# HVGA.net
KiCad netlist of a schematic drawn in Altium Designer
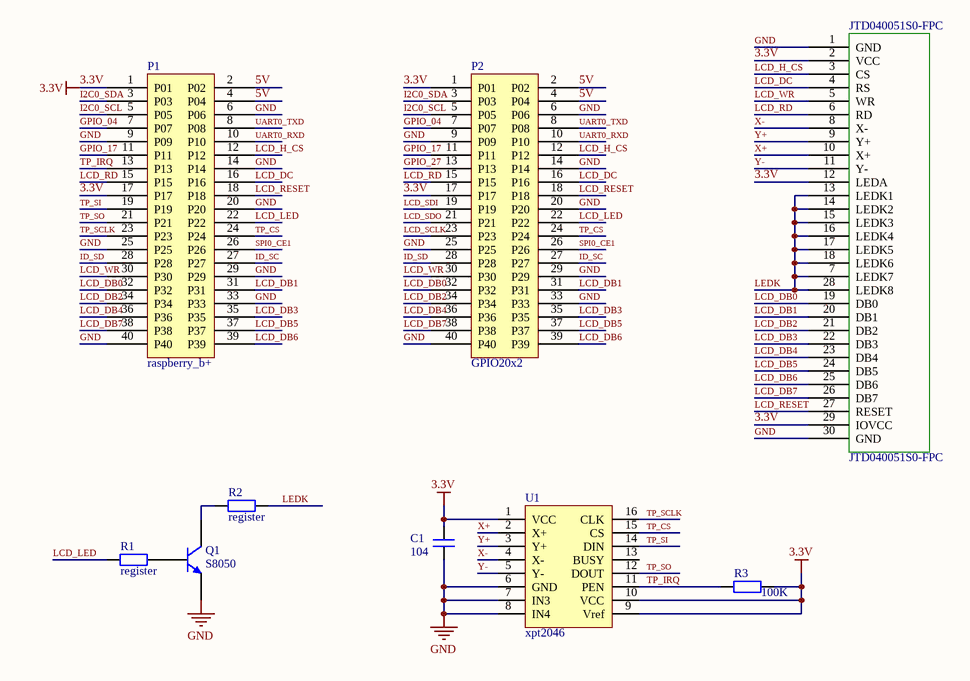
[diagram p0: HVGA.SchDoc]

(export (version "E")
  (design (tool "Eeschema 10.0.6"))
  (components
    (comp (ref "C1") (value "104") (footprint "1206") (libsource (lib "4.0_30P原理图库") (part "capacitor")))
    (comp (ref "JTD040051S0-FPC")
      (value "JTD040051S0-FPC")
      (footprint "JTD040051S0-FPC")
      (libsource (lib "4.0_30P原理图库") (part "JTD040051S0-FPC"))
    )
    (comp (ref "P1")
      (value "raspberry_b+")
      (footprint "raspberry_b+")
      (libsource (lib "4.0_30P原理图库") (part "raspberry_b+"))
    )
    (comp (ref "P2")
      (value "GPIO20x2")
      (footprint "GPIO20x2")
      (libsource (lib "4.0_30P原理图库") (part "raspberry_b+"))
    )
    (comp (ref "Q1") (value "S8050") (footprint "SOT23") (libsource (lib "4.0_30P原理图库") (part "S8050")))
    (comp (ref "R1") (value "register") (footprint "1206") (libsource (lib "4.0_30P原理图库") (part "register")))
    (comp (ref "R2") (value "register") (footprint "1206") (libsource (lib "4.0_30P原理图库") (part "register")))
    (comp (ref "R3") (value "100K") (footprint "1206") (libsource (lib "4.0_30P原理图库") (part "register")))
    (comp (ref "U1") (value "xpt2046") (footprint "TSSOP16") (libsource (lib "4.0_30P原理图库") (part "xpt2046")))
  )
  (nets
    (net (code "1") (name "/5V") (class "Default")
      (node (ref "P1") (pin "2") (pinfunction "P02_2") (pintype "passive"))
      (node (ref "P1") (pin "4") (pinfunction "P04_4") (pintype "passive"))
      (node (ref "P2") (pin "2") (pinfunction "P02_2") (pintype "passive"))
      (node (ref "P2") (pin "4") (pinfunction "P04_4") (pintype "passive"))
    )
    (net (code "2") (name "/GPIO_04") (class "Default")
      (node (ref "P1") (pin "7") (pinfunction "P07_7") (pintype "passive"))
      (node (ref "P2") (pin "7") (pinfunction "P07_7") (pintype "passive"))
    )
    (net (code "3") (name "/GPIO_17") (class "Default")
      (node (ref "P1") (pin "11") (pinfunction "P11_11") (pintype "passive"))
      (node (ref "P2") (pin "11") (pinfunction "P11_11") (pintype "passive"))
    )
    (net (code "4") (name "/GPIO_27") (class "Default")
      (node (ref "P2") (pin "13") (pinfunction "P13_13") (pintype "passive"))
    )
    (net (code "5") (name "/I2C0_SCL") (class "Default")
      (node (ref "P1") (pin "5") (pinfunction "P05_5") (pintype "passive"))
      (node (ref "P2") (pin "5") (pinfunction "P05_5") (pintype "passive"))
    )
    (net (code "6") (name "/I2C0_SDA") (class "Default")
      (node (ref "P1") (pin "3") (pinfunction "P03_3") (pintype "passive"))
      (node (ref "P2") (pin "3") (pinfunction "P03_3") (pintype "passive"))
    )
    (net (code "7") (name "/ID_SC") (class "Default")
      (node (ref "P1") (pin "27") (pinfunction "P27_27") (pintype "passive"))
      (node (ref "P2") (pin "27") (pinfunction "P27_27") (pintype "passive"))
    )
    (net (code "8") (name "/ID_SD") (class "Default")
      (node (ref "P1") (pin "28") (pinfunction "P28_28") (pintype "passive"))
      (node (ref "P2") (pin "28") (pinfunction "P28_28") (pintype "passive"))
    )
    (net (code "9") (name "/LCD_DB0") (class "Default")
      (node (ref "JTD040051S0-FPC") (pin "19") (pinfunction "DB0_19") (pintype "passive"))
      (node (ref "P1") (pin "32") (pinfunction "P32_32") (pintype "passive"))
      (node (ref "P2") (pin "32") (pinfunction "P32_32") (pintype "passive"))
    )
    (net (code "10") (name "/LCD_DB1") (class "Default")
      (node (ref "JTD040051S0-FPC") (pin "20") (pinfunction "DB1_20") (pintype "passive"))
      (node (ref "P1") (pin "31") (pinfunction "P31_31") (pintype "passive"))
      (node (ref "P2") (pin "31") (pinfunction "P31_31") (pintype "passive"))
    )
    (net (code "11") (name "/LCD_DB2") (class "Default")
      (node (ref "JTD040051S0-FPC") (pin "21") (pinfunction "DB2_21") (pintype "passive"))
      (node (ref "P1") (pin "34") (pinfunction "P34_34") (pintype "passive"))
      (node (ref "P2") (pin "34") (pinfunction "P34_34") (pintype "passive"))
    )
    (net (code "12") (name "/LCD_DB3") (class "Default")
      (node (ref "JTD040051S0-FPC") (pin "22") (pinfunction "DB3_22") (pintype "passive"))
      (node (ref "P1") (pin "35") (pinfunction "P35_35") (pintype "passive"))
      (node (ref "P2") (pin "35") (pinfunction "P35_35") (pintype "passive"))
    )
    (net (code "13") (name "/LCD_DB4") (class "Default")
      (node (ref "JTD040051S0-FPC") (pin "23") (pinfunction "DB4_23") (pintype "passive"))
      (node (ref "P1") (pin "36") (pinfunction "P36_36") (pintype "passive"))
      (node (ref "P2") (pin "36") (pinfunction "P36_36") (pintype "passive"))
    )
    (net (code "14") (name "/LCD_DB5") (class "Default")
      (node (ref "JTD040051S0-FPC") (pin "24") (pinfunction "DB5_24") (pintype "passive"))
      (node (ref "P1") (pin "37") (pinfunction "P37_37") (pintype "passive"))
      (node (ref "P2") (pin "37") (pinfunction "P37_37") (pintype "passive"))
    )
    (net (code "15") (name "/LCD_DB6") (class "Default")
      (node (ref "JTD040051S0-FPC") (pin "25") (pinfunction "DB6_25") (pintype "passive"))
      (node (ref "P1") (pin "39") (pinfunction "P39_39") (pintype "passive"))
      (node (ref "P2") (pin "39") (pinfunction "P39_39") (pintype "passive"))
    )
    (net (code "16") (name "/LCD_DB7") (class "Default")
      (node (ref "JTD040051S0-FPC") (pin "26") (pinfunction "DB7_26") (pintype "passive"))
      (node (ref "P1") (pin "38") (pinfunction "P38_38") (pintype "passive"))
      (node (ref "P2") (pin "38") (pinfunction "P38_38") (pintype "passive"))
    )
    (net (code "17") (name "/LCD_DC") (class "Default")
      (node (ref "JTD040051S0-FPC") (pin "4") (pinfunction "RS_4") (pintype "passive"))
      (node (ref "P1") (pin "16") (pinfunction "P16_16") (pintype "passive"))
      (node (ref "P2") (pin "16") (pinfunction "P16_16") (pintype "passive"))
    )
    (net (code "18") (name "/LCD_H_CS") (class "Default")
      (node (ref "JTD040051S0-FPC") (pin "3") (pinfunction "CS_3") (pintype "passive"))
      (node (ref "P1") (pin "12") (pinfunction "P12_12") (pintype "passive"))
      (node (ref "P2") (pin "12") (pinfunction "P12_12") (pintype "passive"))
    )
    (net (code "19") (name "/LCD_LED") (class "Default")
      (node (ref "P1") (pin "22") (pinfunction "P22_22") (pintype "passive"))
      (node (ref "P2") (pin "22") (pinfunction "P22_22") (pintype "passive"))
      (node (ref "R1") (pin "1") (pinfunction "1_1") (pintype "passive"))
    )
    (net (code "20") (name "/LCD_RD") (class "Default")
      (node (ref "JTD040051S0-FPC") (pin "6") (pinfunction "RD_6") (pintype "passive"))
      (node (ref "P1") (pin "15") (pinfunction "P15_15") (pintype "passive"))
      (node (ref "P2") (pin "15") (pinfunction "P15_15") (pintype "passive"))
    )
    (net (code "21") (name "/LCD_RESET") (class "Default")
      (node (ref "JTD040051S0-FPC") (pin "27") (pinfunction "RESET_27") (pintype "passive"))
      (node (ref "P1") (pin "18") (pinfunction "P18_18") (pintype "passive"))
      (node (ref "P2") (pin "18") (pinfunction "P18_18") (pintype "passive"))
    )
    (net (code "22") (name "/LCD_SCLK") (class "Default")
      (node (ref "P2") (pin "23") (pinfunction "P23_23") (pintype "passive"))
    )
    (net (code "23") (name "/LCD_SDI") (class "Default")
      (node (ref "P2") (pin "19") (pinfunction "P19_19") (pintype "passive"))
    )
    (net (code "24") (name "/LCD_SDO") (class "Default")
      (node (ref "P2") (pin "21") (pinfunction "P21_21") (pintype "passive"))
    )
    (net (code "25") (name "/LCD_WR") (class "Default")
      (node (ref "JTD040051S0-FPC") (pin "5") (pinfunction "WR_5") (pintype "passive"))
      (node (ref "P1") (pin "30") (pinfunction "P30_30") (pintype "passive"))
      (node (ref "P2") (pin "30") (pinfunction "P30_30") (pintype "passive"))
    )
    (net (code "26") (name "/LEDK") (class "Default")
      (node (ref "JTD040051S0-FPC") (pin "13") (pinfunction "LEDK1_13") (pintype "passive"))
      (node (ref "JTD040051S0-FPC") (pin "14") (pinfunction "LEDK2_14") (pintype "passive"))
      (node (ref "JTD040051S0-FPC") (pin "15") (pinfunction "LEDK3_15") (pintype "passive"))
      (node (ref "JTD040051S0-FPC") (pin "16") (pinfunction "LEDK4_16") (pintype "passive"))
      (node (ref "JTD040051S0-FPC") (pin "17") (pinfunction "LEDK5_17") (pintype "passive"))
      (node (ref "JTD040051S0-FPC") (pin "18") (pinfunction "LEDK6_18") (pintype "passive"))
      (node (ref "JTD040051S0-FPC") (pin "28") (pinfunction "LEDK8_28") (pintype "passive"))
      (node (ref "JTD040051S0-FPC") (pin "7") (pinfunction "LEDK7_7") (pintype "passive"))
      (node (ref "R2") (pin "2") (pinfunction "2_2") (pintype "passive"))
    )
    (net (code "27") (name "/SPI0_CE1") (class "Default")
      (node (ref "P1") (pin "26") (pinfunction "P26_26") (pintype "passive"))
      (node (ref "P2") (pin "26") (pinfunction "P26_26") (pintype "passive"))
    )
    (net (code "28") (name "/TP_CS") (class "Default")
      (node (ref "P1") (pin "24") (pinfunction "P24_24") (pintype "passive"))
      (node (ref "P2") (pin "24") (pinfunction "P24_24") (pintype "passive"))
      (node (ref "U1") (pin "15") (pinfunction "CS_15") (pintype "passive"))
    )
    (net (code "29") (name "/TP_IRQ") (class "Default")
      (node (ref "P1") (pin "13") (pinfunction "P13_13") (pintype "passive"))
      (node (ref "R3") (pin "1") (pinfunction "1_1") (pintype "passive"))
      (node (ref "U1") (pin "11") (pinfunction "PEN_11") (pintype "passive"))
    )
    (net (code "30") (name "/TP_SCLK") (class "Default")
      (node (ref "P1") (pin "23") (pinfunction "P23_23") (pintype "passive"))
      (node (ref "U1") (pin "16") (pinfunction "CLK_16") (pintype "passive"))
    )
    (net (code "31") (name "/TP_SI") (class "Default")
      (node (ref "P1") (pin "19") (pinfunction "P19_19") (pintype "passive"))
      (node (ref "U1") (pin "14") (pinfunction "DIN_14") (pintype "passive"))
    )
    (net (code "32") (name "/TP_SO") (class "Default")
      (node (ref "P1") (pin "21") (pinfunction "P21_21") (pintype "passive"))
      (node (ref "U1") (pin "12") (pinfunction "DOUT_12") (pintype "passive"))
    )
    (net (code "33") (name "/UART0_RXD") (class "Default")
      (node (ref "P1") (pin "10") (pinfunction "P10_10") (pintype "passive"))
      (node (ref "P2") (pin "10") (pinfunction "P10_10") (pintype "passive"))
    )
    (net (code "34") (name "/UART0_TXD") (class "Default")
      (node (ref "P1") (pin "8") (pinfunction "P08_8") (pintype "passive"))
      (node (ref "P2") (pin "8") (pinfunction "P08_8") (pintype "passive"))
    )
    (net (code "35") (name "/X+") (class "Default")
      (node (ref "JTD040051S0-FPC") (pin "10") (pinfunction "X+_10") (pintype "passive"))
      (node (ref "U1") (pin "2") (pinfunction "X+_2") (pintype "passive"))
    )
    (net (code "36") (name "/X-") (class "Default")
      (node (ref "JTD040051S0-FPC") (pin "8") (pinfunction "X-_8") (pintype "passive"))
      (node (ref "U1") (pin "4") (pinfunction "X-_4") (pintype "passive"))
    )
    (net (code "37") (name "/Y+") (class "Default")
      (node (ref "JTD040051S0-FPC") (pin "9") (pinfunction "Y+_9") (pintype "passive"))
      (node (ref "U1") (pin "3") (pinfunction "Y+_3") (pintype "passive"))
    )
    (net (code "38") (name "/Y-") (class "Default")
      (node (ref "JTD040051S0-FPC") (pin "11") (pinfunction "Y-_11") (pintype "passive"))
      (node (ref "U1") (pin "5") (pinfunction "Y-_5") (pintype "passive"))
    )
    (net (code "39") (name "3.3V") (class "Default")
      (node (ref "C1") (pin "2") (pinfunction "2_2") (pintype "passive"))
      (node (ref "JTD040051S0-FPC") (pin "12") (pinfunction "LEDA_12") (pintype "passive"))
      (node (ref "JTD040051S0-FPC") (pin "2") (pinfunction "VCC_2") (pintype "passive"))
      (node (ref "JTD040051S0-FPC") (pin "29") (pinfunction "IOVCC_29") (pintype "passive"))
      (node (ref "P1") (pin "1") (pinfunction "P01_1") (pintype "passive"))
      (node (ref "P1") (pin "17") (pinfunction "P17_17") (pintype "passive"))
      (node (ref "P2") (pin "1") (pinfunction "P01_1") (pintype "passive"))
      (node (ref "P2") (pin "17") (pinfunction "P17_17") (pintype "passive"))
      (node (ref "R3") (pin "2") (pinfunction "2_2") (pintype "passive"))
      (node (ref "U1") (pin "1") (pinfunction "VCC_1") (pintype "passive"))
      (node (ref "U1") (pin "10") (pinfunction "VCC_10") (pintype "passive"))
      (node (ref "U1") (pin "9") (pinfunction "Vref_9") (pintype "passive"))
    )
    (net (code "40") (name "GND") (class "Default")
      (node (ref "C1") (pin "1") (pinfunction "1_1") (pintype "passive"))
      (node (ref "JTD040051S0-FPC") (pin "1") (pinfunction "GND_1") (pintype "passive"))
      (node (ref "JTD040051S0-FPC") (pin "30") (pinfunction "GND_30") (pintype "passive"))
      (node (ref "P1") (pin "14") (pinfunction "P14_14") (pintype "passive"))
      (node (ref "P1") (pin "20") (pinfunction "P20_20") (pintype "passive"))
      (node (ref "P1") (pin "25") (pinfunction "P25_25") (pintype "passive"))
      (node (ref "P1") (pin "29") (pinfunction "P29_29") (pintype "passive"))
      (node (ref "P1") (pin "33") (pinfunction "P33_33") (pintype "passive"))
      (node (ref "P1") (pin "40") (pinfunction "P40_40") (pintype "passive"))
      (node (ref "P1") (pin "6") (pinfunction "P06_6") (pintype "passive"))
      (node (ref "P1") (pin "9") (pinfunction "P09_9") (pintype "passive"))
      (node (ref "P2") (pin "14") (pinfunction "P14_14") (pintype "passive"))
      (node (ref "P2") (pin "20") (pinfunction "P20_20") (pintype "passive"))
      (node (ref "P2") (pin "25") (pinfunction "P25_25") (pintype "passive"))
      (node (ref "P2") (pin "29") (pinfunction "P29_29") (pintype "passive"))
      (node (ref "P2") (pin "33") (pinfunction "P33_33") (pintype "passive"))
      (node (ref "P2") (pin "40") (pinfunction "P40_40") (pintype "passive"))
      (node (ref "P2") (pin "6") (pinfunction "P06_6") (pintype "passive"))
      (node (ref "P2") (pin "9") (pinfunction "P09_9") (pintype "passive"))
      (node (ref "Q1") (pin "1") (pinfunction "E_1") (pintype "passive"))
      (node (ref "U1") (pin "6") (pinfunction "GND_6") (pintype "passive"))
      (node (ref "U1") (pin "7") (pinfunction "IN3_7") (pintype "passive"))
      (node (ref "U1") (pin "8") (pinfunction "IN4_8") (pintype "passive"))
    )
    (net (code "41") (name "Net-(Q1-B)") (class "Default")
      (node (ref "Q1") (pin "2") (pinfunction "B_2") (pintype "passive"))
      (node (ref "R1") (pin "2") (pinfunction "2_2") (pintype "passive"))
    )
    (net (code "42") (name "Net-(Q1-C)") (class "Default")
      (node (ref "Q1") (pin "3") (pinfunction "C_3") (pintype "passive"))
      (node (ref "R2") (pin "1") (pinfunction "1_1") (pintype "passive"))
    )
    (net (code "43") (name "unconnected-(U1-BUSY-Pad13)") (class "Default")
      (node (ref "U1") (pin "13") (pinfunction "BUSY_13") (pintype "passive"))
    )
  )
)
